# Power.net
KiCad netlist of a schematic drawn in EAGLE
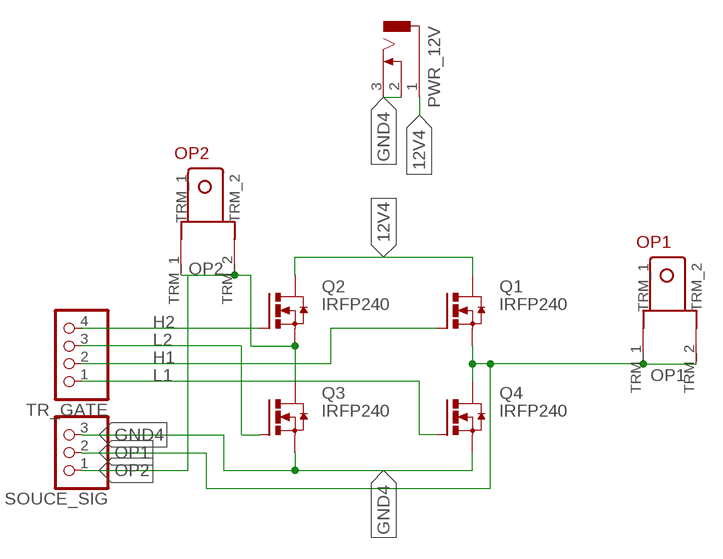
[diagram p0: schematic, sheet 1]

(export (version "E")
  (design (tool "Eeschema 10.0.6"))
  (components
    (comp (ref "OP1")
      (value "TERMINAL_EDITED")
      (footprint "eagle-import:TERMINAL_EDITED")
      (libsource (lib "eagle-import") (part "TERMINAL_EDITED"))
    )
    (comp (ref "OP2")
      (value "TERMINAL_EDITED")
      (footprint "eagle-import:TERMINAL_EDITED")
      (libsource (lib "eagle-import") (part "TERMINAL_EDITED"))
    )
    (comp (ref "PWR_12V")
      (value "CON_JACK")
      (footprint "eagle-import:DCJ0303")
      (libsource (lib "eagle-import") (part "CON_JACK"))
    )
    (comp (ref "Q1")
      (value "IRFP240")
      (footprint "eagle-import:TO247BV")
      (libsource (lib "eagle-import") (part "IRFP240"))
    )
    (comp (ref "Q2")
      (value "IRFP240")
      (footprint "eagle-import:TO247BV")
      (libsource (lib "eagle-import") (part "IRFP240"))
    )
    (comp (ref "Q3")
      (value "IRFP240")
      (footprint "eagle-import:TO247BV")
      (libsource (lib "eagle-import") (part "IRFP240"))
    )
    (comp (ref "Q4")
      (value "IRFP240")
      (footprint "eagle-import:TO247BV")
      (libsource (lib "eagle-import") (part "IRFP240"))
    )
    (comp (ref "SOUCE_SIG")
      (value "PINHD-1X3")
      (footprint "eagle-import:1X03")
      (libsource (lib "eagle-import") (part "PINHD-1X3"))
    )
    (comp (ref "TR_GATE")
      (value "PINHD-1X4")
      (footprint "eagle-import:1X04")
      (libsource (lib "eagle-import") (part "PINHD-1X4"))
    )
  )
  (nets
    (net (code "1") (name "/H1") (class "Default")
      (node (ref "Q1") (pin "G") (pinfunction "G_G") (pintype "passive"))
      (node (ref "TR_GATE") (pin "2") (pinfunction "2_2") (pintype "passive"))
    )
    (net (code "2") (name "/H2") (class "Default")
      (node (ref "Q2") (pin "G") (pinfunction "G_G") (pintype "passive"))
      (node (ref "TR_GATE") (pin "4") (pinfunction "4_4") (pintype "passive"))
    )
    (net (code "3") (name "/L1") (class "Default")
      (node (ref "Q4") (pin "G") (pinfunction "G_G") (pintype "passive"))
      (node (ref "TR_GATE") (pin "1") (pinfunction "1_1") (pintype "passive"))
    )
    (net (code "4") (name "/L2") (class "Default")
      (node (ref "Q3") (pin "G") (pinfunction "G_G") (pintype "passive"))
      (node (ref "TR_GATE") (pin "3") (pinfunction "3_3") (pintype "passive"))
    )
    (net (code "5") (name "12V4") (class "Default")
      (node (ref "PWR_12V") (pin "1") (pinfunction "1_1") (pintype "passive"))
      (node (ref "Q1") (pin "D") (pinfunction "D_D") (pintype "passive"))
      (node (ref "Q2") (pin "D") (pinfunction "D_D") (pintype "passive"))
    )
    (net (code "6") (name "GND4") (class "Default")
      (node (ref "PWR_12V") (pin "2") (pinfunction "2_2") (pintype "passive"))
      (node (ref "PWR_12V") (pin "3") (pinfunction "3_3") (pintype "passive"))
      (node (ref "Q3") (pin "S") (pinfunction "S_S") (pintype "passive"))
      (node (ref "Q4") (pin "S") (pinfunction "S_S") (pintype "passive"))
      (node (ref "SOUCE_SIG") (pin "3") (pinfunction "3_3") (pintype "passive"))
    )
    (net (code "7") (name "OP1") (class "Default")
      (node (ref "OP1") (pin "TRM_1") (pinfunction "TRM_1_TRM_1") (pintype "bidirectional"))
      (node (ref "OP1") (pin "TRM_2") (pinfunction "TRM_2_TRM_2") (pintype "bidirectional"))
      (node (ref "Q1") (pin "S") (pinfunction "S_S") (pintype "passive"))
      (node (ref "Q4") (pin "D") (pinfunction "D_D") (pintype "passive"))
      (node (ref "SOUCE_SIG") (pin "2") (pinfunction "2_2") (pintype "passive"))
    )
    (net (code "8") (name "OP2") (class "Default")
      (node (ref "OP2") (pin "TRM_1") (pinfunction "TRM_1_TRM_1") (pintype "bidirectional"))
      (node (ref "OP2") (pin "TRM_2") (pinfunction "TRM_2_TRM_2") (pintype "bidirectional"))
      (node (ref "Q2") (pin "S") (pinfunction "S_S") (pintype "passive"))
      (node (ref "Q3") (pin "D") (pinfunction "D_D") (pintype "passive"))
      (node (ref "SOUCE_SIG") (pin "1") (pinfunction "1_1") (pintype "passive"))
    )
  )
)
